# Schematic_EasyEDA_file.net
KiCad netlist of a schematic drawn in EasyEDA
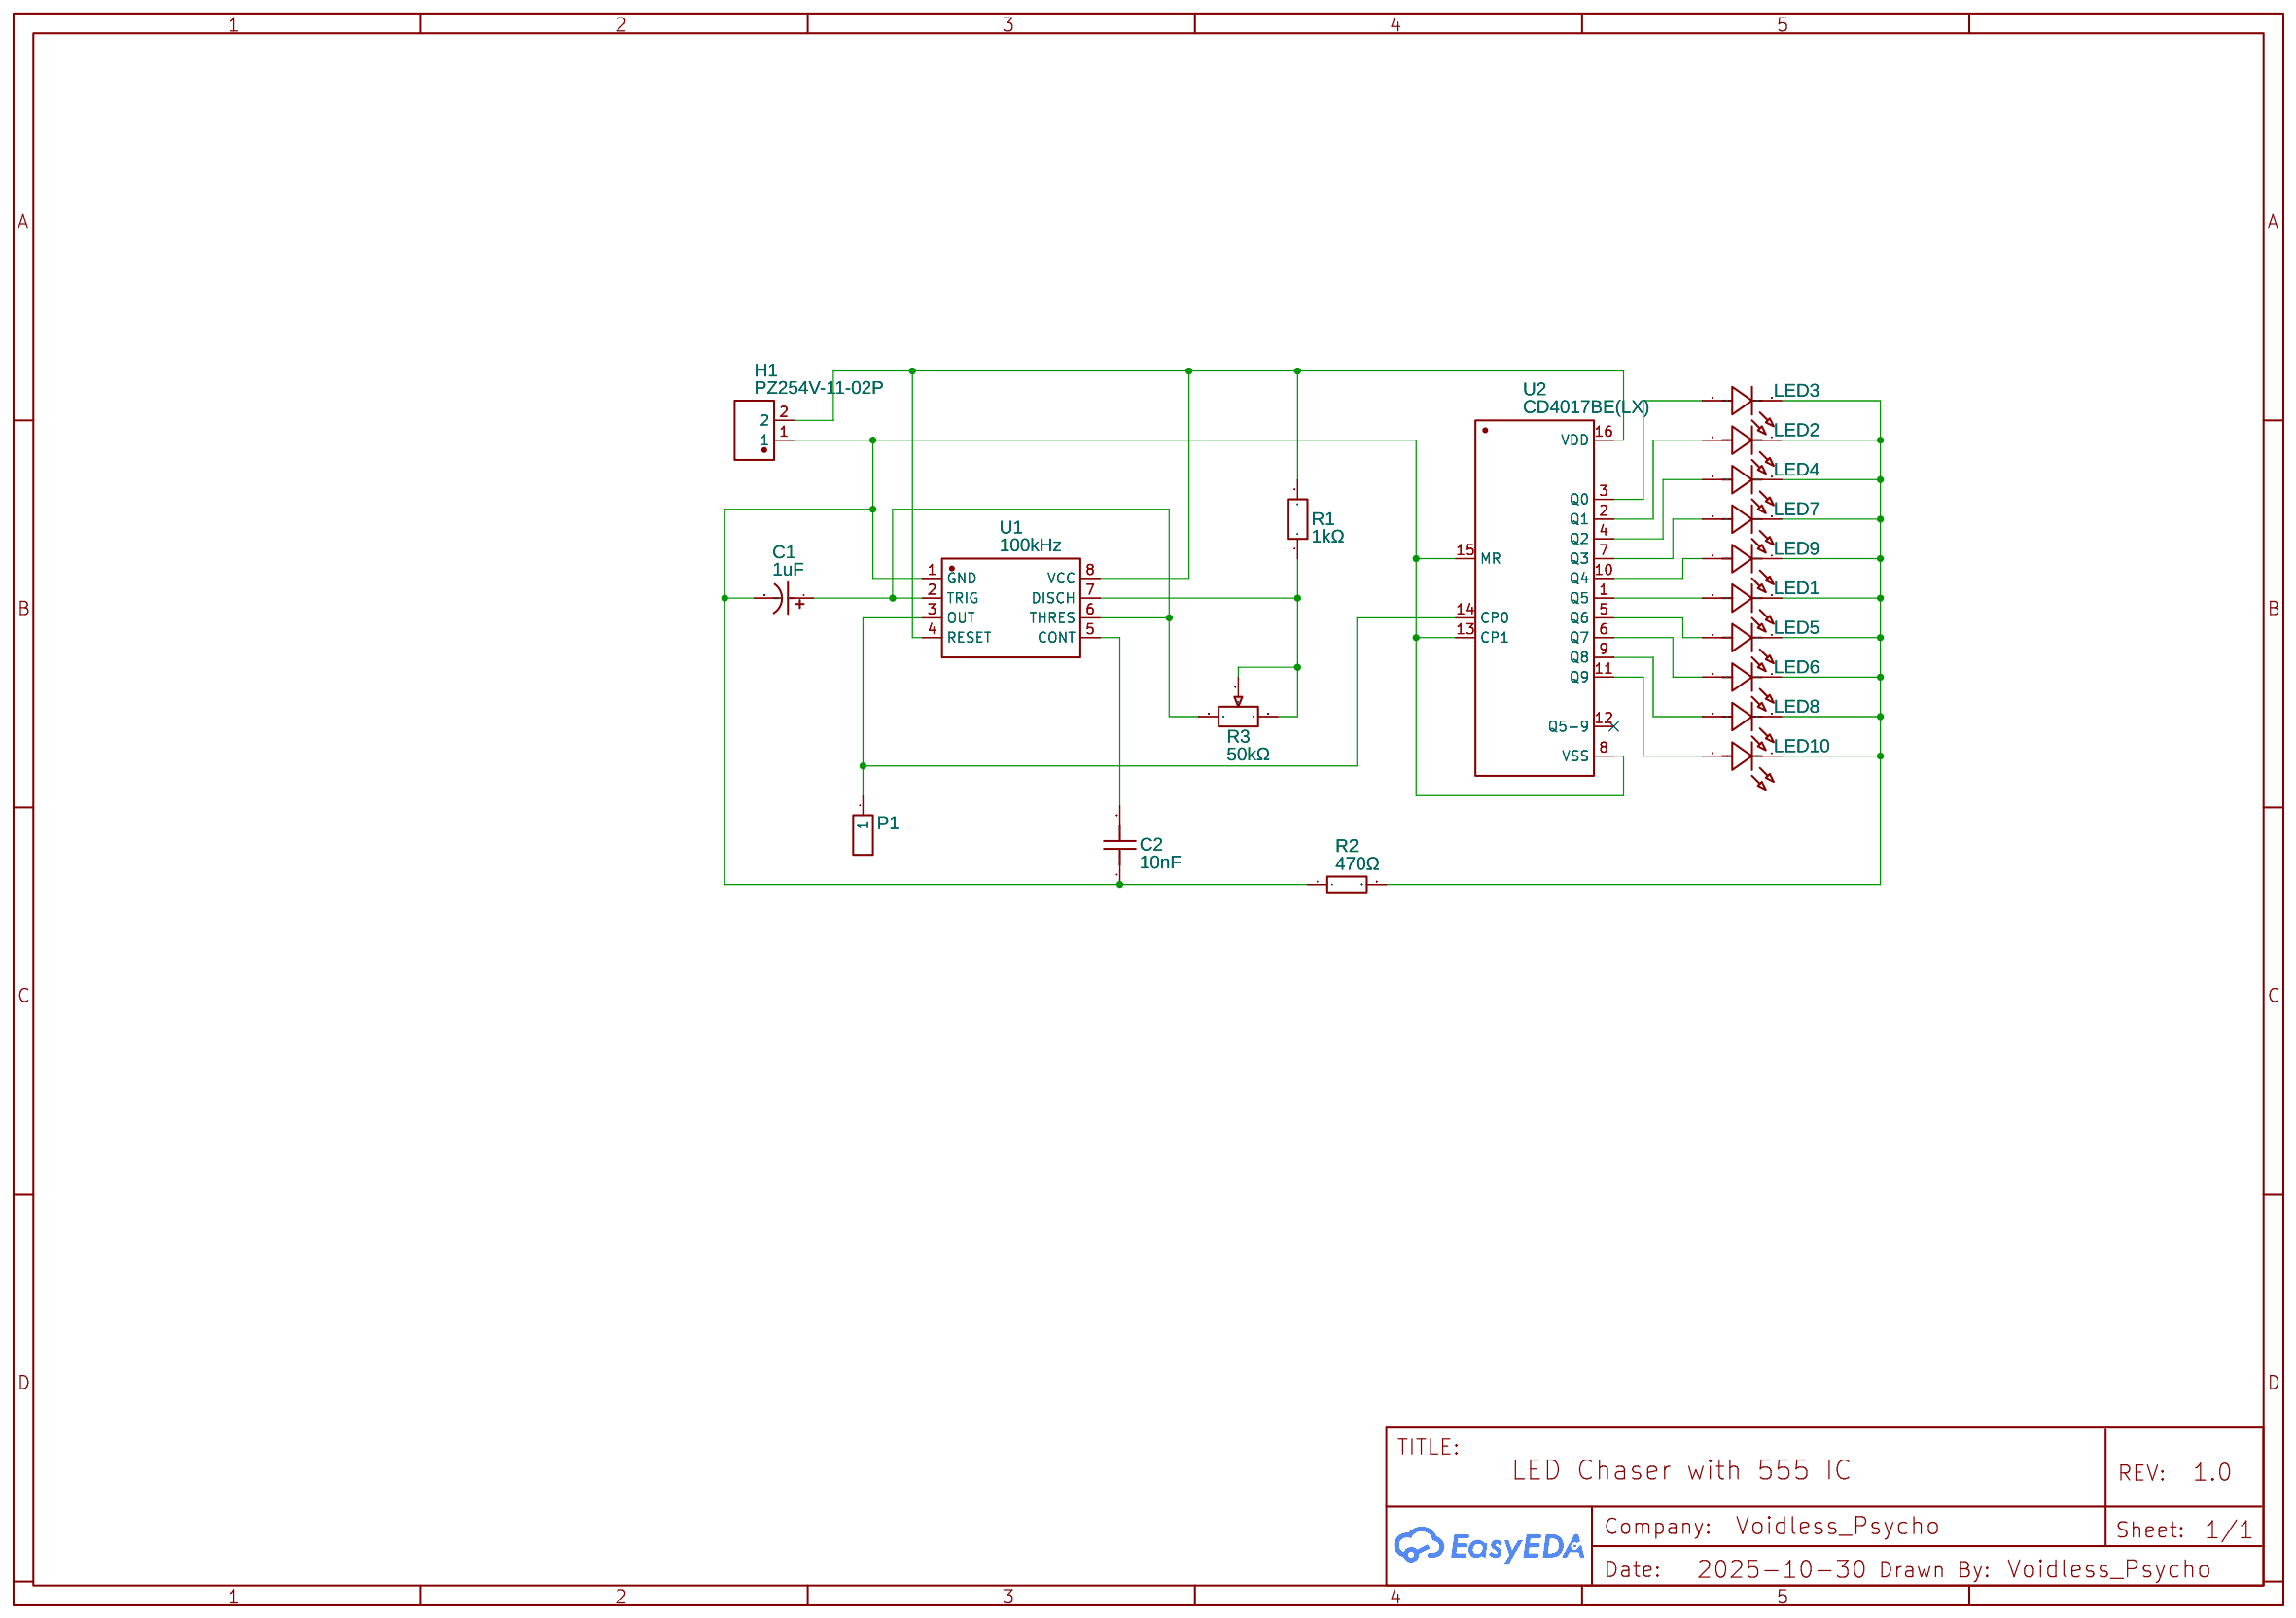
[diagram p0: schematic sheet]

(export (version "E")
  (design (tool "Eeschema 10.0.6"))
  (components
    (comp (ref "C1")
      (value "1uF")
      (fields (field (name "Manufacturer Part") "KF010M050C110A") (field (name "Manufacturer") "CapXon(丰宾)"))
      (libsource (lib "") (part "KF010M050C110A"))
    )
    (comp (ref "C2")
      (value "10nF")
      (fields (field (name "Manufacturer Part") "N09F1B103MN0B0S0N0") (field (name "Manufacturer") "STE(松田)"))
      (libsource (lib "") (part "N09F1B103MN0B0S0N0"))
    )
    (comp (ref "H1")
      (value "PZ254V-11-02P")
      (fields (field (name "Manufacturer") "XFCN(兴飞)"))
      (libsource (lib "") (part "PZ254V-11-02P"))
    )
    (comp (ref "LED1")
      (value "XL-502UWC")
      (fields (field (name "Manufacturer") "XINGLIGHT(成兴光)"))
      (libsource (lib "") (part "XL-502UWC"))
    )
    (comp (ref "LED2")
      (value "XL-502UWC")
      (fields (field (name "Manufacturer") "XINGLIGHT(成兴光)"))
      (libsource (lib "") (part "XL-502UWC"))
    )
    (comp (ref "LED3")
      (value "XL-502UWC")
      (fields (field (name "Manufacturer") "XINGLIGHT(成兴光)"))
      (libsource (lib "") (part "XL-502UWC"))
    )
    (comp (ref "LED4")
      (value "XL-502UWC")
      (fields (field (name "Manufacturer") "XINGLIGHT(成兴光)"))
      (libsource (lib "") (part "XL-502UWC"))
    )
    (comp (ref "LED5")
      (value "XL-502UWC")
      (fields (field (name "Manufacturer") "XINGLIGHT(成兴光)"))
      (libsource (lib "") (part "XL-502UWC"))
    )
    (comp (ref "LED6")
      (value "XL-502UWC")
      (fields (field (name "Manufacturer") "XINGLIGHT(成兴光)"))
      (libsource (lib "") (part "XL-502UWC"))
    )
    (comp (ref "LED7")
      (value "XL-502UWC")
      (fields (field (name "Manufacturer") "XINGLIGHT(成兴光)"))
      (libsource (lib "") (part "XL-502UWC"))
    )
    (comp (ref "LED8")
      (value "XL-502UWC")
      (fields (field (name "Manufacturer") "XINGLIGHT(成兴光)"))
      (libsource (lib "") (part "XL-502UWC"))
    )
    (comp (ref "LED9")
      (value "XL-502UWC")
      (fields (field (name "Manufacturer") "XINGLIGHT(成兴光)"))
      (libsource (lib "") (part "XL-502UWC"))
    )
    (comp (ref "LED10")
      (value "XL-502UWC")
      (fields (field (name "Manufacturer") "XINGLIGHT(成兴光)"))
      (libsource (lib "") (part "XL-502UWC"))
    )
    (comp (ref "P1")
      (value "Header-Male-2.54_1x1")
      (fields (field (name "Manufacturer Part") "2.54-1*1P针") (field (name "Manufacturer") "BOOMELE(博穆精密)"))
      (libsource (lib "") (part "Header-Male-2.54_1x1"))
    )
    (comp (ref "R1")
      (value "1kΩ")
      (fields (field (name "Manufacturer Part") "MF1/4W-1KΩ±1%T52") (field (name "Manufacturer") "华星机电"))
      (libsource (lib "") (part "MF1/4W-1KΩ±1%T52"))
    )
    (comp (ref "R2")
      (value "470Ω")
      (fields
        (field (name "Manufacturer Part") "MFR0W4F4700A50")
        (field (name "Manufacturer") "UNI-ROYAL(厚声)")
      )
      (libsource (lib "") (part "MFR0W4F4700A50"))
    )
    (comp (ref "R3")
      (value "50kΩ")
      (fields (field (name "Manufacturer Part") "3296X-1-503") (field (name "Manufacturer") "BOCHEN(博晨)"))
      (libsource (lib "") (part "3296X-1-503_C118912"))
    )
    (comp (ref "U1")
      (value "100kHz")
      (fields (field (name "Manufacturer Part") "NE555P") (field (name "Manufacturer") "TI(德州仪器)"))
      (libsource (lib "") (part "NE555P"))
    )
    (comp (ref "U2")
      (value "CD4017BE(LX)")
      (fields (field (name "Manufacturer") "LX(灵星芯微)"))
      (libsource (lib "") (part "CD4017BE(LX)"))
    )
  )
  (nets
    (net (code "1") (name "Net-(LED1-A)") (class "Default")
      (node (ref "LED1") (pin "2") (pinfunction "A_2") (pintype "unspecified"))
      (node (ref "U2") (pin "1") (pinfunction "Q5_1") (pintype "unspecified"))
    )
    (net (code "2") (name "Net-(LED1-K)") (class "Default")
      (node (ref "LED1") (pin "1") (pinfunction "K_1") (pintype "unspecified"))
      (node (ref "LED10") (pin "1") (pinfunction "K_1") (pintype "unspecified"))
      (node (ref "LED2") (pin "1") (pinfunction "K_1") (pintype "unspecified"))
      (node (ref "LED3") (pin "1") (pinfunction "K_1") (pintype "unspecified"))
      (node (ref "LED4") (pin "1") (pinfunction "K_1") (pintype "unspecified"))
      (node (ref "LED5") (pin "1") (pinfunction "K_1") (pintype "unspecified"))
      (node (ref "LED6") (pin "1") (pinfunction "K_1") (pintype "unspecified"))
      (node (ref "LED7") (pin "1") (pinfunction "K_1") (pintype "unspecified"))
      (node (ref "LED8") (pin "1") (pinfunction "K_1") (pintype "unspecified"))
      (node (ref "LED9") (pin "1") (pinfunction "K_1") (pintype "unspecified"))
      (node (ref "R2") (pin "2") (pinfunction "2_2") (pintype "input"))
    )
    (net (code "3") (name "Net-(LED2-A)") (class "Default")
      (node (ref "LED2") (pin "2") (pinfunction "A_2") (pintype "unspecified"))
      (node (ref "U2") (pin "2") (pinfunction "Q1_2") (pintype "unspecified"))
    )
    (net (code "4") (name "Net-(LED3-A)") (class "Default")
      (node (ref "LED3") (pin "2") (pinfunction "A_2") (pintype "unspecified"))
      (node (ref "U2") (pin "3") (pinfunction "Q0_3") (pintype "unspecified"))
    )
    (net (code "5") (name "Net-(LED4-A)") (class "Default")
      (node (ref "LED4") (pin "2") (pinfunction "A_2") (pintype "unspecified"))
      (node (ref "U2") (pin "4") (pinfunction "Q2_4") (pintype "unspecified"))
    )
    (net (code "6") (name "Net-(LED5-A)") (class "Default")
      (node (ref "LED5") (pin "2") (pinfunction "A_2") (pintype "unspecified"))
      (node (ref "U2") (pin "5") (pinfunction "Q6_5") (pintype "unspecified"))
    )
    (net (code "7") (name "Net-(LED6-A)") (class "Default")
      (node (ref "LED6") (pin "2") (pinfunction "A_2") (pintype "unspecified"))
      (node (ref "U2") (pin "6") (pinfunction "Q7_6") (pintype "unspecified"))
    )
    (net (code "8") (name "Net-(LED7-A)") (class "Default")
      (node (ref "LED7") (pin "2") (pinfunction "A_2") (pintype "unspecified"))
      (node (ref "U2") (pin "7") (pinfunction "Q3_7") (pintype "unspecified"))
    )
    (net (code "9") (name "Net-(LED8-A)") (class "Default")
      (node (ref "LED8") (pin "2") (pinfunction "A_2") (pintype "unspecified"))
      (node (ref "U2") (pin "9") (pinfunction "Q8_9") (pintype "unspecified"))
    )
    (net (code "10") (name "Net-(LED9-A)") (class "Default")
      (node (ref "LED9") (pin "2") (pinfunction "A_2") (pintype "unspecified"))
      (node (ref "U2") (pin "10") (pinfunction "Q4_10") (pintype "unspecified"))
    )
    (net (code "11") (name "Net-(LED10-A)") (class "Default")
      (node (ref "LED10") (pin "2") (pinfunction "A_2") (pintype "unspecified"))
      (node (ref "U2") (pin "11") (pinfunction "Q9_11") (pintype "unspecified"))
    )
    (net (code "12") (name "Net-(U1-CONT)") (class "Default")
      (node (ref "C2") (pin "2") (pinfunction "2_2") (pintype "unspecified"))
      (node (ref "U1") (pin "5") (pinfunction "CONT_5") (pintype "unspecified"))
    )
    (net (code "13") (name "Net-(U1-DISCH)") (class "Default")
      (node (ref "R1") (pin "1") (pinfunction "1_1") (pintype "unspecified"))
      (node (ref "R3") (pin "2") (pinfunction "2_2") (pintype "input"))
      (node (ref "R3") (pin "3") (pinfunction "3_3") (pintype "input"))
      (node (ref "U1") (pin "7") (pinfunction "DISCH_7") (pintype "unspecified"))
    )
    (net (code "14") (name "Net-(U1-GND)") (class "Default")
      (node (ref "C1") (pin "2") (pinfunction "2_2") (pintype "input"))
      (node (ref "C2") (pin "1") (pinfunction "1_1") (pintype "unspecified"))
      (node (ref "H1") (pin "1") (pinfunction "1_1") (pintype "unspecified"))
      (node (ref "R2") (pin "1") (pinfunction "1_1") (pintype "input"))
      (node (ref "U1") (pin "1") (pinfunction "GND_1") (pintype "unspecified"))
      (node (ref "U2") (pin "13") (pinfunction "CP1_13") (pintype "unspecified"))
      (node (ref "U2") (pin "15") (pinfunction "MR_15") (pintype "unspecified"))
      (node (ref "U2") (pin "8") (pinfunction "VSS_8") (pintype "unspecified"))
    )
    (net (code "15") (name "Net-(U1-OUT)") (class "Default")
      (node (ref "P1") (pin "1") (pinfunction "1_1") (pintype "input"))
      (node (ref "U1") (pin "3") (pinfunction "OUT_3") (pintype "unspecified"))
      (node (ref "U2") (pin "14") (pinfunction "CP0_14") (pintype "unspecified"))
    )
    (net (code "16") (name "Net-(U1-RESET)") (class "Default")
      (node (ref "H1") (pin "2") (pinfunction "2_2") (pintype "unspecified"))
      (node (ref "R1") (pin "2") (pinfunction "2_2") (pintype "unspecified"))
      (node (ref "U1") (pin "4") (pinfunction "RESET_4") (pintype "unspecified"))
      (node (ref "U1") (pin "8") (pinfunction "VCC_8") (pintype "unspecified"))
      (node (ref "U2") (pin "16") (pinfunction "VDD_16") (pintype "unspecified"))
    )
    (net (code "17") (name "Net-(U1-THRES)") (class "Default")
      (node (ref "C1") (pin "1") (pinfunction "1_1") (pintype "input"))
      (node (ref "R3") (pin "1") (pinfunction "1_1") (pintype "input"))
      (node (ref "U1") (pin "2") (pinfunction "TRIG_2") (pintype "unspecified"))
      (node (ref "U1") (pin "6") (pinfunction "THRES_6") (pintype "unspecified"))
    )
    (net (code "18") (name "unconnected-(U2-Q5-9-Pad12)") (class "Default")
      (node (ref "U2") (pin "12") (pinfunction "Q5-9_12") (pintype "unspecified+no_connect"))
    )
  )
)
